# 4HP_2181_VCA.net
KiCad netlist of a schematic drawn in EAGLE
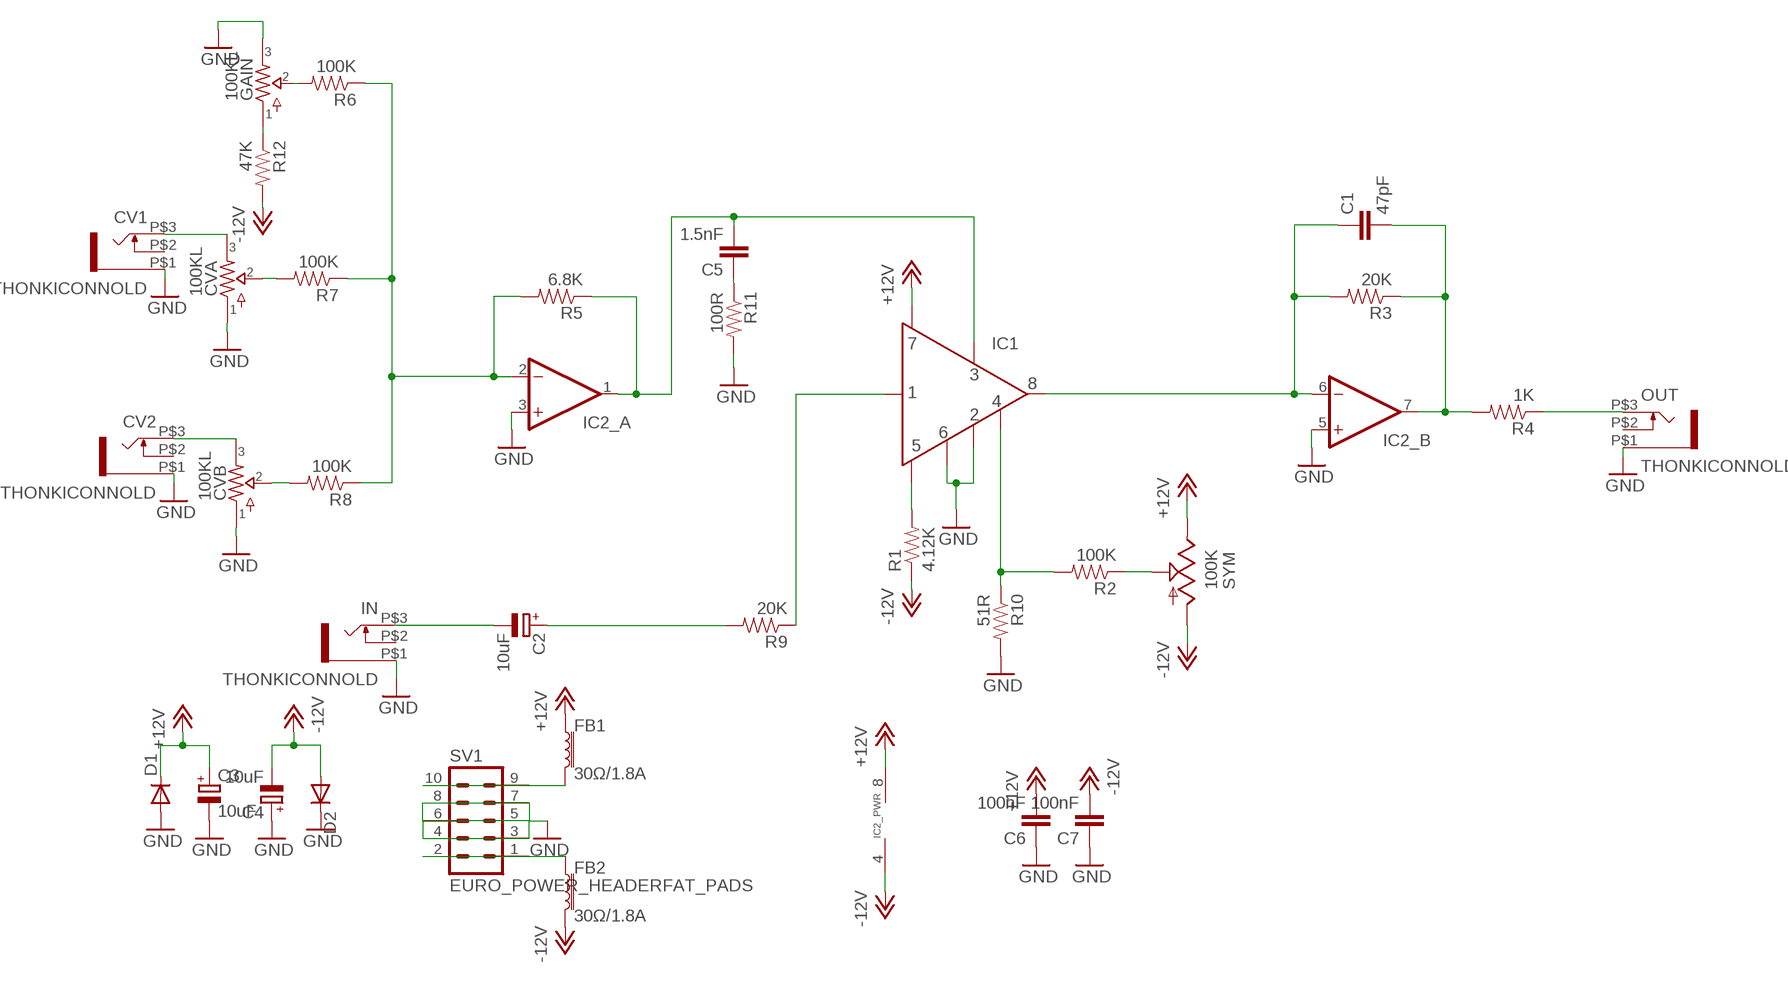
[diagram p0: schematic, sheet 1]

(export (version "E")
  (design (tool "Eeschema 10.0.6"))
  (components
    (comp (ref "C1")
      (value "47pF")
      (footprint "eagle-import:0603-CAP")
      (libsource (lib "eagle-import") (part "CAP0603-CAP"))
    )
    (comp (ref "C2")
      (value "10uF")
      (footprint "eagle-import:CASE_B")
      (libsource (lib "eagle-import") (part "CAPACITOR_POL-CASE_B"))
    )
    (comp (ref "C3")
      (value "10uF")
      (footprint "eagle-import:CASE_B")
      (libsource (lib "eagle-import") (part "CAPACITOR_POL-CASE_B"))
    )
    (comp (ref "C4")
      (value "10uF")
      (footprint "eagle-import:CASE_B")
      (libsource (lib "eagle-import") (part "CAPACITOR_POL-CASE_B"))
    )
    (comp (ref "C5")
      (value "1.5nF")
      (footprint "eagle-import:0603-CAP")
      (libsource (lib "eagle-import") (part "CAP0603-CAP"))
    )
    (comp (ref "C6")
      (value "100nF")
      (footprint "eagle-import:0603-CAP")
      (libsource (lib "eagle-import") (part "CAP0603-CAP"))
    )
    (comp (ref "C7")
      (value "100nF")
      (footprint "eagle-import:0603-CAP")
      (libsource (lib "eagle-import") (part "CAP0603-CAP"))
    )
    (comp (ref "CV1")
      (value "THONKICONNOLD")
      (footprint "eagle-import:THONKICONN")
      (libsource (lib "eagle-import") (part "THONKICONNOLD"))
    )
    (comp (ref "CV2")
      (value "THONKICONNOLD")
      (footprint "eagle-import:THONKICONN")
      (libsource (lib "eagle-import") (part "THONKICONNOLD"))
    )
    (comp (ref "CVA")
      (value "100KL")
      (footprint "eagle-import:9MM_W_MOUNTS-2MMHOLES")
      (libsource (lib "eagle-import") (part "POTS9MM_MOUNTED_2MMH"))
    )
    (comp (ref "CVB")
      (value "100KL")
      (footprint "eagle-import:9MM_W_MOUNTS-2MMHOLES")
      (libsource (lib "eagle-import") (part "POTS9MM_MOUNTED_2MMH"))
    )
    (comp (ref "D1")
      (value "DIODE-SOD-123")
      (footprint "eagle-import:SOD-123")
      (libsource (lib "eagle-import") (part "DIODE-SOD-123"))
    )
    (comp (ref "D2")
      (value "DIODE-SOD-123")
      (footprint "eagle-import:SOD-123")
      (libsource (lib "eagle-import") (part "DIODE-SOD-123"))
    )
    (comp (ref "FB1")
      (value "30Ω/1.8A")
      (footprint "eagle-import:0603")
      (libsource (lib "eagle-import") (part "FERRITE_BEAD-0603"))
    )
    (comp (ref "FB2")
      (value "30Ω/1.8A")
      (footprint "eagle-import:0603")
      (libsource (lib "eagle-import") (part "FERRITE_BEAD-0603"))
    )
    (comp (ref "GAIN")
      (value "100KL")
      (footprint "eagle-import:9MM_W_MOUNTS-2MMHOLES")
      (libsource (lib "eagle-import") (part "POTS9MM_MOUNTED_2MMH"))
    )
    (comp (ref "IC1")
      (value "THAT2181C")
      (footprint "eagle-import:SIL8")
      (libsource (lib "eagle-import") (part "THAT2181C"))
    )
    (comp (ref "IC2")
      (value "DUALSMD")
      (footprint "eagle-import:SO08")
      (libsource (lib "eagle-import") (part "DUALSMD"))
    )
    (comp (ref "IN")
      (value "THONKICONNOLD")
      (footprint "eagle-import:THONKICONN")
      (libsource (lib "eagle-import") (part "THONKICONNOLD"))
    )
    (comp (ref "OUT")
      (value "THONKICONNOLD")
      (footprint "eagle-import:THONKICONN")
      (libsource (lib "eagle-import") (part "THONKICONNOLD"))
    )
    (comp (ref "R1")
      (value "4.12K")
      (footprint "eagle-import:0603-RES")
      (libsource (lib "eagle-import") (part "RESISTOR0603-RES"))
    )
    (comp (ref "R2")
      (value "100K")
      (footprint "eagle-import:0603-RES")
      (libsource (lib "eagle-import") (part "RESISTOR0603-RES"))
    )
    (comp (ref "R3")
      (value "20K")
      (footprint "eagle-import:0603-RES")
      (libsource (lib "eagle-import") (part "RESISTOR0603-RES"))
    )
    (comp (ref "R4")
      (value "1K")
      (footprint "eagle-import:0603-RES")
      (libsource (lib "eagle-import") (part "RESISTOR0603-RES"))
    )
    (comp (ref "R5")
      (value "6.8K")
      (footprint "eagle-import:0603-RES")
      (libsource (lib "eagle-import") (part "RESISTOR0603-RES"))
    )
    (comp (ref "R6")
      (value "100K")
      (footprint "eagle-import:0603-RES")
      (libsource (lib "eagle-import") (part "RESISTOR0603-RES"))
    )
    (comp (ref "R7")
      (value "100K")
      (footprint "eagle-import:0603-RES")
      (libsource (lib "eagle-import") (part "RESISTOR0603-RES"))
    )
    (comp (ref "R8")
      (value "100K")
      (footprint "eagle-import:0603-RES")
      (libsource (lib "eagle-import") (part "RESISTOR0603-RES"))
    )
    (comp (ref "R9")
      (value "20K")
      (footprint "eagle-import:0603-RES")
      (libsource (lib "eagle-import") (part "RESISTOR0603-RES"))
    )
    (comp (ref "R10")
      (value "51R")
      (footprint "eagle-import:0603-RES")
      (libsource (lib "eagle-import") (part "RESISTOR0603-RES"))
    )
    (comp (ref "R11")
      (value "100R")
      (footprint "eagle-import:0603-RES")
      (libsource (lib "eagle-import") (part "RESISTOR0603-RES"))
    )
    (comp (ref "R12")
      (value "47K")
      (footprint "eagle-import:0603-RES")
      (libsource (lib "eagle-import") (part "RESISTOR0603-RES"))
    )
    (comp (ref "SV1")
      (value "EURO_POWER_HEADERFAT_PADS")
      (footprint "eagle-import:EURO_PWR_HEADER_FAT")
      (libsource (lib "eagle-import") (part "EURO_POWER_HEADERFAT_PADS"))
    )
    (comp (ref "SYM")
      (value "100K")
      (footprint "eagle-import:S64W")
      (libsource (lib "eagle-import") (part "TRIM_US-S64W"))
    )
  )
  (nets
    (net (code "1") (name "+12V") (class "Default")
      (node (ref "C3") (pin "+") (pinfunction "+_+") (pintype "passive"))
      (node (ref "C6") (pin "2") (pinfunction "2_2") (pintype "passive"))
      (node (ref "D1") (pin "C") (pinfunction "C_C") (pintype "passive"))
      (node (ref "FB1") (pin "1") (pinfunction "1_1") (pintype "passive"))
      (node (ref "IC1") (pin "7") (pinfunction "P$7_7") (pintype "bidirectional"))
      (node (ref "IC2") (pin "8") (pinfunction "V+_8") (pintype "power_in"))
      (node (ref "SYM") (pin "E") (pinfunction "E_E") (pintype "passive"))
    )
    (net (code "2") (name "-12V") (class "Default")
      (node (ref "C4") (pin "-") (pinfunction "-_-") (pintype "passive"))
      (node (ref "C7") (pin "2") (pinfunction "2_2") (pintype "passive"))
      (node (ref "D2") (pin "A") (pinfunction "A_A") (pintype "passive"))
      (node (ref "FB2") (pin "2") (pinfunction "2_2") (pintype "passive"))
      (node (ref "IC2") (pin "4") (pinfunction "V-_4") (pintype "power_in"))
      (node (ref "R1") (pin "1") (pinfunction "1_1") (pintype "passive"))
      (node (ref "R12") (pin "2") (pinfunction "2_2") (pintype "passive"))
      (node (ref "SYM") (pin "A") (pinfunction "A_A") (pintype "passive"))
    )
    (net (code "3") (name "GND") (class "Default")
      (node (ref "C3") (pin "-") (pinfunction "-_-") (pintype "passive"))
      (node (ref "C4") (pin "+") (pinfunction "+_+") (pintype "passive"))
      (node (ref "C6") (pin "1") (pinfunction "1_1") (pintype "passive"))
      (node (ref "C7") (pin "1") (pinfunction "1_1") (pintype "passive"))
      (node (ref "CV1") (pin "P$1") (pinfunction "5_P$1") (pintype "passive"))
      (node (ref "CV2") (pin "P$1") (pinfunction "5_P$1") (pintype "passive"))
      (node (ref "CVA") (pin "P$1") (pinfunction "1_P$1") (pintype "passive"))
      (node (ref "CVB") (pin "P$1") (pinfunction "1_P$1") (pintype "passive"))
      (node (ref "D1") (pin "A") (pinfunction "A_A") (pintype "passive"))
      (node (ref "D2") (pin "C") (pinfunction "C_C") (pintype "passive"))
      (node (ref "GAIN") (pin "P$3") (pinfunction "3_P$3") (pintype "passive"))
      (node (ref "IC1") (pin "2") (pinfunction "P$2_2") (pintype "bidirectional"))
      (node (ref "IC1") (pin "6") (pinfunction "P$6_6") (pintype "bidirectional"))
      (node (ref "IC2") (pin "3") (pinfunction "+IN_3") (pintype "input"))
      (node (ref "IC2") (pin "5") (pinfunction "+IN_5") (pintype "input"))
      (node (ref "IN") (pin "P$1") (pinfunction "5_P$1") (pintype "passive"))
      (node (ref "OUT") (pin "P$1") (pinfunction "5_P$1") (pintype "passive"))
      (node (ref "R10") (pin "2") (pinfunction "2_2") (pintype "passive"))
      (node (ref "R11") (pin "2") (pinfunction "2_2") (pintype "passive"))
      (node (ref "SV1") (pin "3") (pinfunction "3_3") (pintype "passive"))
      (node (ref "SV1") (pin "4") (pinfunction "4_4") (pintype "passive"))
      (node (ref "SV1") (pin "5") (pinfunction "5_5") (pintype "passive"))
      (node (ref "SV1") (pin "6") (pinfunction "6_6") (pintype "passive"))
      (node (ref "SV1") (pin "7") (pinfunction "7_7") (pintype "passive"))
      (node (ref "SV1") (pin "8") (pinfunction "8_8") (pintype "passive"))
    )
    (net (code "4") (name "Net-(C2-Pad+)") (class "Default")
      (node (ref "C2") (pin "+") (pinfunction "+_+") (pintype "passive"))
      (node (ref "R9") (pin "2") (pinfunction "2_2") (pintype "passive"))
    )
    (net (code "5") (name "Net-(C5-Pad1)") (class "Default")
      (node (ref "C5") (pin "1") (pinfunction "1_1") (pintype "passive"))
      (node (ref "R11") (pin "1") (pinfunction "1_1") (pintype "passive"))
    )
    (net (code "6") (name "Net-(CV1-3)") (class "Default")
      (node (ref "CV1") (pin "P$3") (pinfunction "3_P$3") (pintype "passive"))
      (node (ref "CVA") (pin "P$3") (pinfunction "3_P$3") (pintype "passive"))
    )
    (net (code "7") (name "Net-(CV2-3)") (class "Default")
      (node (ref "CV2") (pin "P$3") (pinfunction "3_P$3") (pintype "passive"))
      (node (ref "CVB") (pin "P$3") (pinfunction "3_P$3") (pintype "passive"))
    )
    (net (code "8") (name "Net-(CVA-2)") (class "Default")
      (node (ref "CVA") (pin "P$2") (pinfunction "2_P$2") (pintype "passive"))
      (node (ref "R7") (pin "2") (pinfunction "2_2") (pintype "passive"))
    )
    (net (code "9") (name "Net-(CVB-2)") (class "Default")
      (node (ref "CVB") (pin "P$2") (pinfunction "2_P$2") (pintype "passive"))
      (node (ref "R8") (pin "2") (pinfunction "2_2") (pintype "passive"))
    )
    (net (code "10") (name "Net-(FB1-Pad2)") (class "Default")
      (node (ref "FB1") (pin "2") (pinfunction "2_2") (pintype "passive"))
      (node (ref "SV1") (pin "10") (pinfunction "10_10") (pintype "passive"))
      (node (ref "SV1") (pin "9") (pinfunction "9_9") (pintype "passive"))
    )
    (net (code "11") (name "Net-(FB2-Pad1)") (class "Default")
      (node (ref "FB2") (pin "1") (pinfunction "1_1") (pintype "passive"))
      (node (ref "SV1") (pin "1") (pinfunction "1_1") (pintype "passive"))
      (node (ref "SV1") (pin "2") (pinfunction "2_2") (pintype "passive"))
    )
    (net (code "12") (name "Net-(GAIN-1)") (class "Default")
      (node (ref "GAIN") (pin "P$1") (pinfunction "1_P$1") (pintype "passive"))
      (node (ref "R12") (pin "1") (pinfunction "1_1") (pintype "passive"))
    )
    (net (code "13") (name "Net-(GAIN-2)") (class "Default")
      (node (ref "GAIN") (pin "P$2") (pinfunction "2_P$2") (pintype "passive"))
      (node (ref "R6") (pin "2") (pinfunction "2_2") (pintype "passive"))
    )
    (net (code "14") (name "Net-(IC1-P$1)") (class "Default")
      (node (ref "IC1") (pin "1") (pinfunction "P$1_1") (pintype "bidirectional"))
      (node (ref "R9") (pin "1") (pinfunction "1_1") (pintype "passive"))
    )
    (net (code "15") (name "Net-(IC1-P$3)") (class "Default")
      (node (ref "C5") (pin "2") (pinfunction "2_2") (pintype "passive"))
      (node (ref "IC1") (pin "3") (pinfunction "P$3_3") (pintype "bidirectional"))
      (node (ref "IC2") (pin "1") (pinfunction "OUT_1") (pintype "output"))
      (node (ref "R5") (pin "1") (pinfunction "1_1") (pintype "passive"))
    )
    (net (code "16") (name "Net-(IC1-P$4)") (class "Default")
      (node (ref "IC1") (pin "4") (pinfunction "P$4_4") (pintype "bidirectional"))
      (node (ref "R10") (pin "1") (pinfunction "1_1") (pintype "passive"))
      (node (ref "R2") (pin "2") (pinfunction "2_2") (pintype "passive"))
    )
    (net (code "17") (name "Net-(IC1-P$5)") (class "Default")
      (node (ref "IC1") (pin "5") (pinfunction "P$5_5") (pintype "bidirectional"))
      (node (ref "R1") (pin "2") (pinfunction "2_2") (pintype "passive"))
    )
    (net (code "18") (name "Net-(IC1-P$8)") (class "Default")
      (node (ref "C1") (pin "1") (pinfunction "1_1") (pintype "passive"))
      (node (ref "IC1") (pin "8") (pinfunction "P$8_8") (pintype "bidirectional"))
      (node (ref "IC2") (pin "6") (pinfunction "-IN_6") (pintype "input"))
      (node (ref "R3") (pin "2") (pinfunction "2_2") (pintype "passive"))
    )
    (net (code "19") (name "Net-(IC2A--IN)") (class "Default")
      (node (ref "IC2") (pin "2") (pinfunction "-IN_2") (pintype "input"))
      (node (ref "R5") (pin "2") (pinfunction "2_2") (pintype "passive"))
      (node (ref "R6") (pin "1") (pinfunction "1_1") (pintype "passive"))
      (node (ref "R7") (pin "1") (pinfunction "1_1") (pintype "passive"))
      (node (ref "R8") (pin "1") (pinfunction "1_1") (pintype "passive"))
    )
    (net (code "20") (name "Net-(IC2B-OUT)") (class "Default")
      (node (ref "C1") (pin "2") (pinfunction "2_2") (pintype "passive"))
      (node (ref "IC2") (pin "7") (pinfunction "OUT_7") (pintype "output"))
      (node (ref "R3") (pin "1") (pinfunction "1_1") (pintype "passive"))
      (node (ref "R4") (pin "2") (pinfunction "2_2") (pintype "passive"))
    )
    (net (code "21") (name "Net-(IN-3)") (class "Default")
      (node (ref "C2") (pin "-") (pinfunction "-_-") (pintype "passive"))
      (node (ref "IN") (pin "P$3") (pinfunction "3_P$3") (pintype "passive"))
    )
    (net (code "22") (name "Net-(OUT-3)") (class "Default")
      (node (ref "OUT") (pin "P$3") (pinfunction "3_P$3") (pintype "passive"))
      (node (ref "R4") (pin "1") (pinfunction "1_1") (pintype "passive"))
    )
    (net (code "23") (name "Net-(R2-Pad1)") (class "Default")
      (node (ref "R2") (pin "1") (pinfunction "1_1") (pintype "passive"))
      (node (ref "SYM") (pin "S") (pinfunction "S_S") (pintype "passive"))
    )
    (net (code "24") (name "unconnected-(CV1-4-PadP$2)") (class "Default")
      (node (ref "CV1") (pin "P$2") (pinfunction "4_P$2") (pintype "passive"))
    )
    (net (code "25") (name "unconnected-(CV2-4-PadP$2)") (class "Default")
      (node (ref "CV2") (pin "P$2") (pinfunction "4_P$2") (pintype "passive"))
    )
    (net (code "26") (name "unconnected-(IN-4-PadP$2)") (class "Default")
      (node (ref "IN") (pin "P$2") (pinfunction "4_P$2") (pintype "passive"))
    )
    (net (code "27") (name "unconnected-(OUT-4-PadP$2)") (class "Default")
      (node (ref "OUT") (pin "P$2") (pinfunction "4_P$2") (pintype "passive"))
    )
  )
)
